# DP_TO_HDMI.net
KiCad netlist of a schematic drawn in Altium Designer
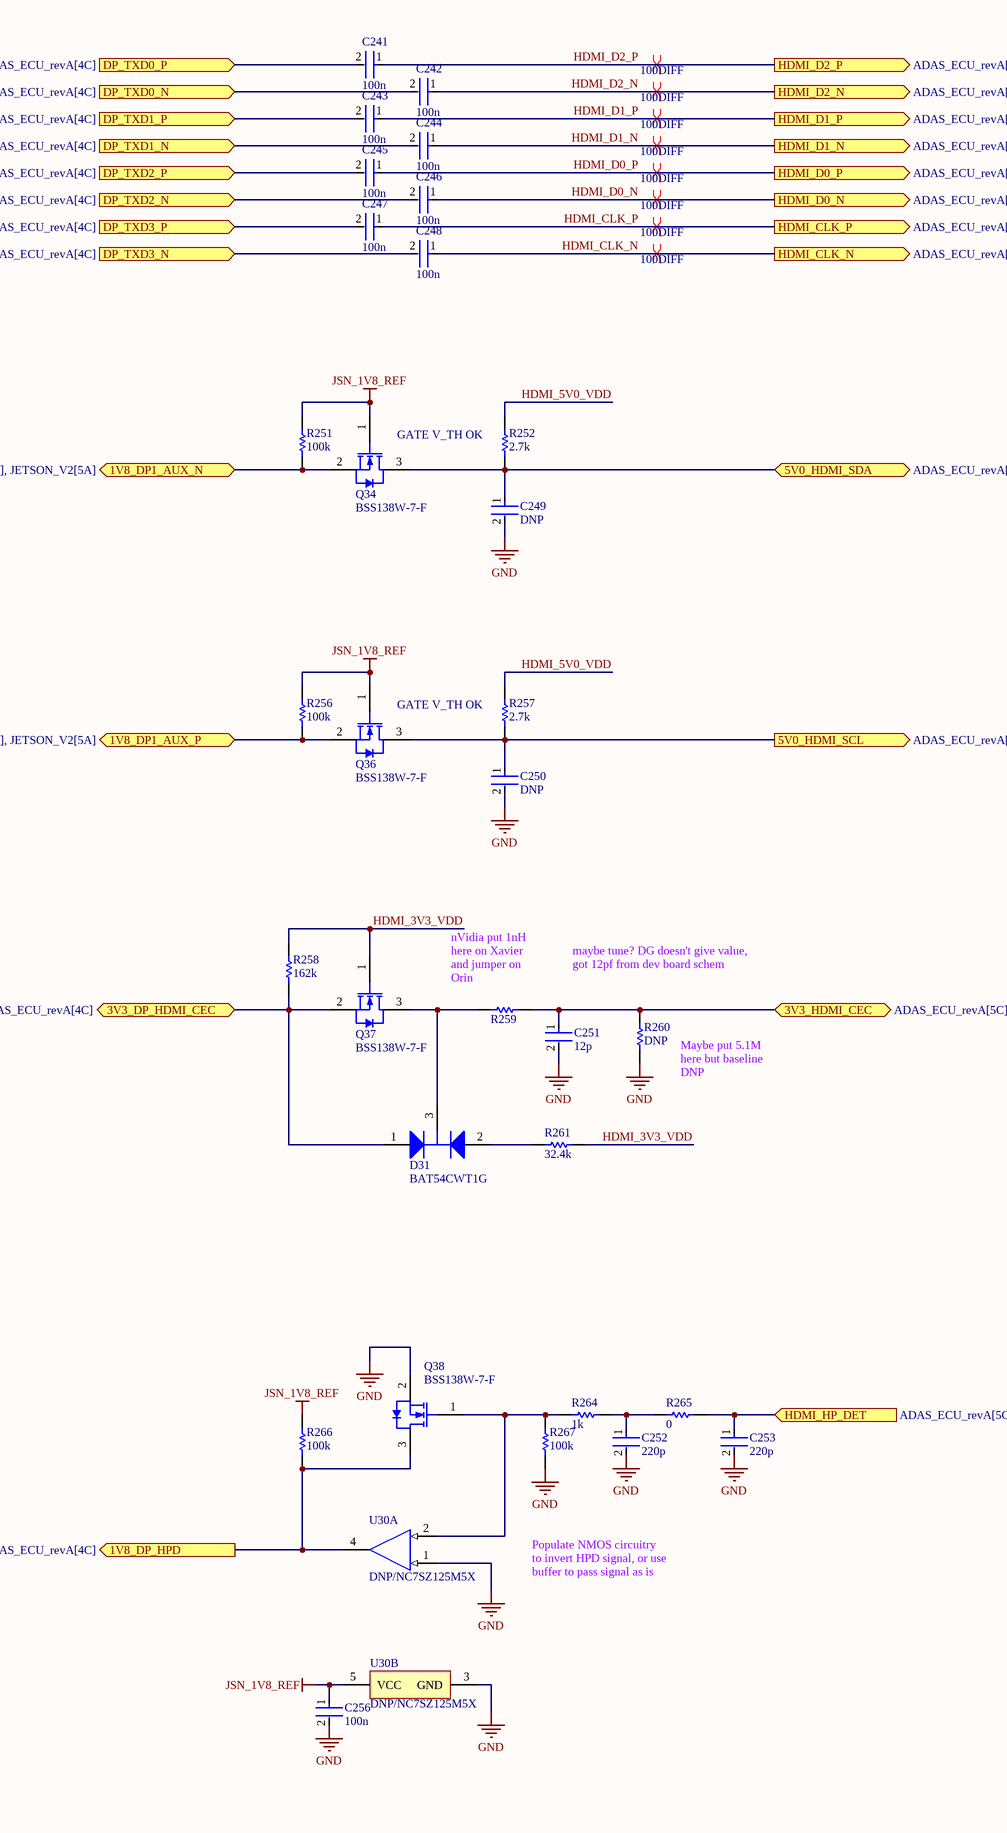
[diagram p0: DP_TO_HDMI.SchDoc, left]
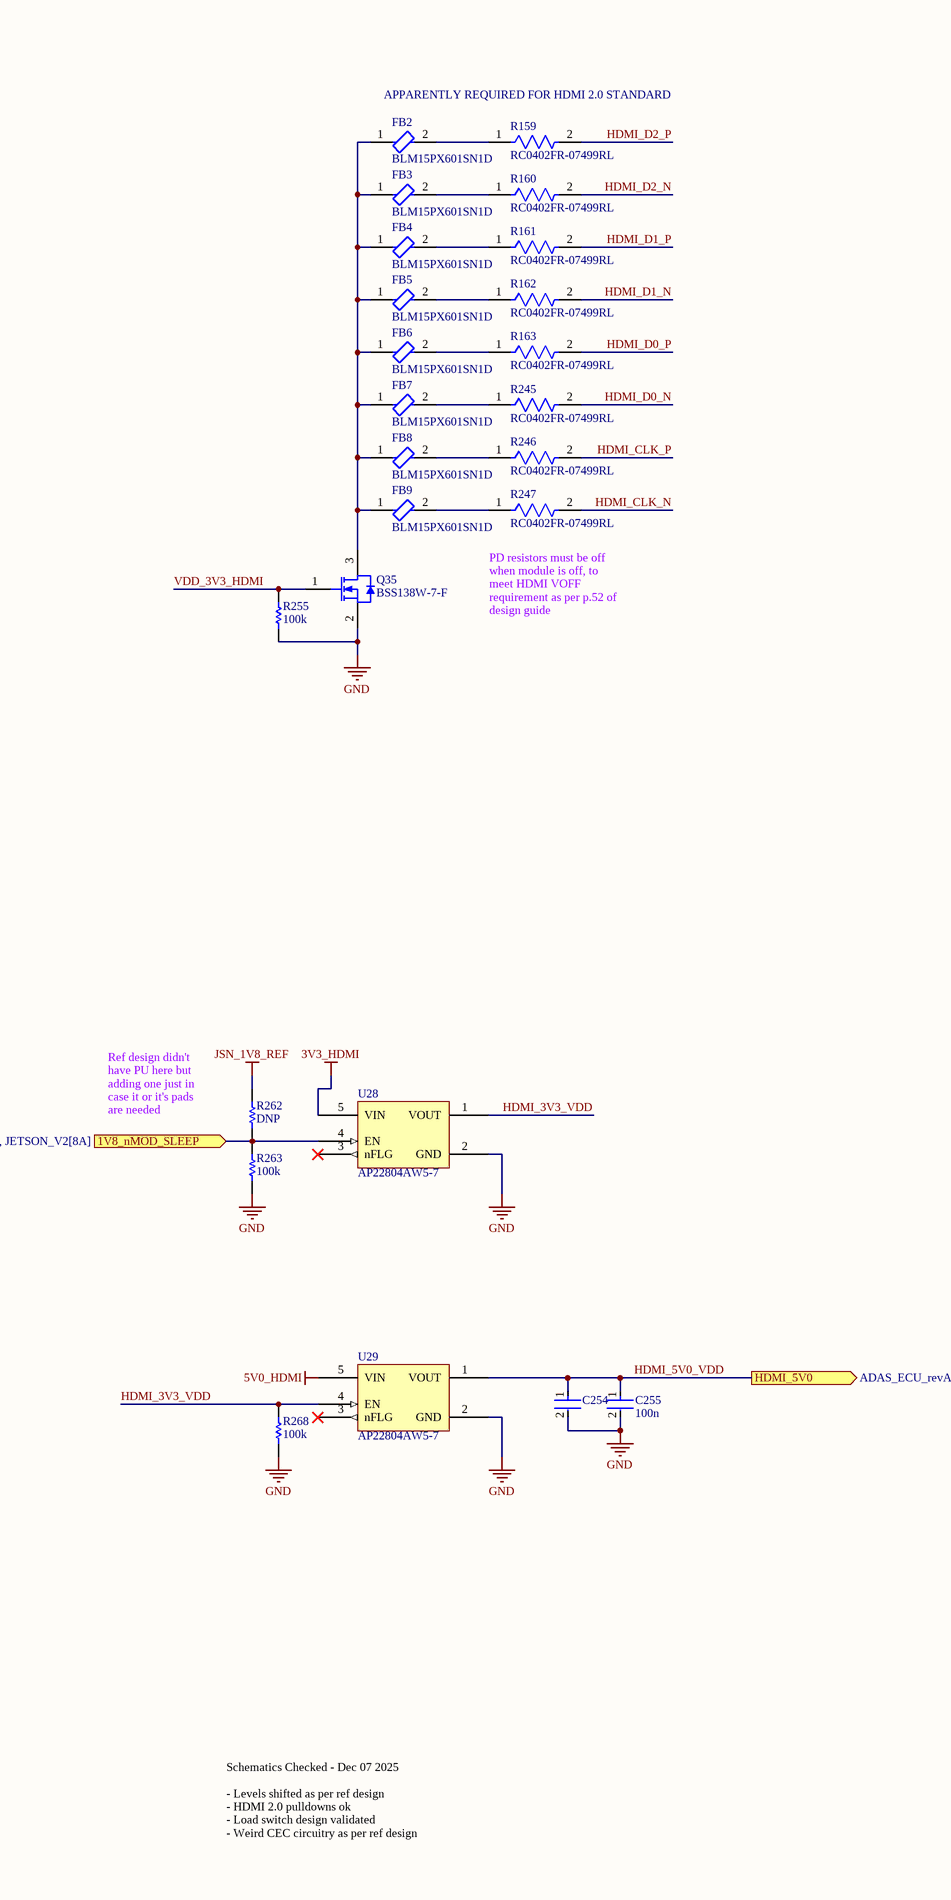
[diagram p1: DP_TO_HDMI.SchDoc, right]

(export (version "E")
  (design (tool "Eeschema 10.0.6"))
  (components
    (comp (ref "C241")
      (value "100n")
      (footprint "FP-0402-L_1_0_0_05-W_0_5-IPC_A")
      (description "LARGE PADS, 0402 CAP, CHANGE COMMENT TO MATCH REAL P/N")
      (libsource (lib "Space Concordia") (part "b4654b650e69147ec39a6b967a45e02"))
    )
    (comp (ref "C242")
      (value "100n")
      (footprint "FP-0402-L_1_0_0_05-W_0_5-IPC_A")
      (description "LARGE PADS, 0402 CAP, CHANGE COMMENT TO MATCH REAL P/N")
      (libsource (lib "Space Concordia") (part "b4654b650e69147ec39a6b967a45e02"))
    )
    (comp (ref "C243")
      (value "100n")
      (footprint "FP-0402-L_1_0_0_05-W_0_5-IPC_A")
      (description "LARGE PADS, 0402 CAP, CHANGE COMMENT TO MATCH REAL P/N")
      (libsource (lib "Space Concordia") (part "b4654b650e69147ec39a6b967a45e02"))
    )
    (comp (ref "C244")
      (value "100n")
      (footprint "FP-0402-L_1_0_0_05-W_0_5-IPC_A")
      (description "LARGE PADS, 0402 CAP, CHANGE COMMENT TO MATCH REAL P/N")
      (libsource (lib "Space Concordia") (part "b4654b650e69147ec39a6b967a45e02"))
    )
    (comp (ref "C245")
      (value "100n")
      (footprint "FP-0402-L_1_0_0_05-W_0_5-IPC_A")
      (description "LARGE PADS, 0402 CAP, CHANGE COMMENT TO MATCH REAL P/N")
      (libsource (lib "Space Concordia") (part "b4654b650e69147ec39a6b967a45e02"))
    )
    (comp (ref "C246")
      (value "100n")
      (footprint "FP-0402-L_1_0_0_05-W_0_5-IPC_A")
      (description "LARGE PADS, 0402 CAP, CHANGE COMMENT TO MATCH REAL P/N")
      (libsource (lib "Space Concordia") (part "b4654b650e69147ec39a6b967a45e02"))
    )
    (comp (ref "C247")
      (value "100n")
      (footprint "FP-0402-L_1_0_0_05-W_0_5-IPC_A")
      (description "LARGE PADS, 0402 CAP, CHANGE COMMENT TO MATCH REAL P/N")
      (libsource (lib "Space Concordia") (part "b4654b650e69147ec39a6b967a45e02"))
    )
    (comp (ref "C248")
      (value "100n")
      (footprint "FP-0402-L_1_0_0_05-W_0_5-IPC_A")
      (description "LARGE PADS, 0402 CAP, CHANGE COMMENT TO MATCH REAL P/N")
      (libsource (lib "Space Concordia") (part "b4654b650e69147ec39a6b967a45e02"))
    )
    (comp (ref "C249")
      (value "DNP")
      (footprint "FP-0402-L_1_0_0_05-W_0_5-IPC_A")
      (description "LARGE PADS, 0402 CAP, CHANGE COMMENT TO MATCH REAL P/N")
      (libsource (lib "Space Concordia") (part "b4654b650e69147ec39a6b967a45e02"))
    )
    (comp (ref "C250")
      (value "DNP")
      (footprint "FP-0402-L_1_0_0_05-W_0_5-IPC_A")
      (description "LARGE PADS, 0402 CAP, CHANGE COMMENT TO MATCH REAL P/N")
      (libsource (lib "Space Concordia") (part "b4654b650e69147ec39a6b967a45e02"))
    )
    (comp (ref "C251")
      (value "12p")
      (footprint "FP-0402-L_1_0_0_05-W_0_5-IPC_A")
      (description "LARGE PADS, 0402 CAP, CHANGE COMMENT TO MATCH REAL P/N")
      (libsource (lib "Space Concordia") (part "b4654b650e69147ec39a6b967a45e02"))
    )
    (comp (ref "C252")
      (value "220p")
      (footprint "FP-0402-L_1_0_0_05-W_0_5-IPC_A")
      (description "LARGE PADS, 0402 CAP, CHANGE COMMENT TO MATCH REAL P/N")
      (libsource (lib "Space Concordia") (part "b4654b650e69147ec39a6b967a45e02"))
    )
    (comp (ref "C253")
      (value "220p")
      (footprint "FP-0402-L_1_0_0_05-W_0_5-IPC_A")
      (description "LARGE PADS, 0402 CAP, CHANGE COMMENT TO MATCH REAL P/N")
      (libsource (lib "Space Concordia") (part "b4654b650e69147ec39a6b967a45e02"))
    )
    (comp (ref "C254")
      (value "DNP/GRM188R60J106ME47D")
      (footprint "FP-GRM188-0_1-e0_2_0_55-IPC_A")
      (description "Chip Multilayer Ceramic Capacitors for General Purpose, 0603, 10uF, X5R, 15%, 20%, 6.3V")
      (fields (field (name "VOLTAGE") "6.3V") (field (name "TOLERANCE") "20%"))
      (libsource (lib "Altium Content Vault") (part "02cd4be3c70576c341d710602a673aa"))
    )
    (comp (ref "C255")
      (value "100n")
      (footprint "FP-0402-L_1_0_0_05-W_0_5-IPC_A")
      (description "LARGE PADS, 0402 CAP, CHANGE COMMENT TO MATCH REAL P/N")
      (libsource (lib "Space Concordia") (part "b4654b650e69147ec39a6b967a45e02"))
    )
    (comp (ref "C256")
      (value "100n")
      (footprint "FP-0402-L_1_0_0_05-W_0_5-IPC_A")
      (description "LARGE PADS, 0402 CAP, CHANGE COMMENT TO MATCH REAL P/N")
      (libsource (lib "Space Concordia") (part "b4654b650e69147ec39a6b967a45e02"))
    )
    (comp (ref "D31")
      (value "BAT54CWT1G")
      (footprint "ONSC-SOT-323-3-419-04_V")
      (description "Dual Series Cathode Schottky Barrier Diodes, 3-Pin SOT-323, Pb-Free, Tape and Reel")
      (fields (field (name "MANUFACTURER") "On Semiconductor"))
      (libsource (lib "Altium Content Vault") (part "ONSC-D-A1A2K3-3"))
    )
    (comp (ref "FB2")
      (value "BLM15PX601SN1D")
      (footprint "FP-BLM15-0_05-MFG")
      (description "Chip Ferrite Bead, 0402, 600Ω @ 100MHz, 0.23Ω, 25%, 900mA")
      (fields (field (name "TOLERANCE") "25%"))
      (libsource (lib "Altium Content Vault") (part "5f30dd21d616792df468990f7003faa"))
    )
    (comp (ref "FB3")
      (value "BLM15PX601SN1D")
      (footprint "FP-BLM15-0_05-MFG")
      (description "Chip Ferrite Bead, 0402, 600Ω @ 100MHz, 0.23Ω, 25%, 900mA")
      (fields (field (name "TOLERANCE") "25%"))
      (libsource (lib "Altium Content Vault") (part "5f30dd21d616792df468990f7003faa"))
    )
    (comp (ref "FB4")
      (value "BLM15PX601SN1D")
      (footprint "FP-BLM15-0_05-MFG")
      (description "Chip Ferrite Bead, 0402, 600Ω @ 100MHz, 0.23Ω, 25%, 900mA")
      (fields (field (name "TOLERANCE") "25%"))
      (libsource (lib "Altium Content Vault") (part "5f30dd21d616792df468990f7003faa"))
    )
    (comp (ref "FB5")
      (value "BLM15PX601SN1D")
      (footprint "FP-BLM15-0_05-MFG")
      (description "Chip Ferrite Bead, 0402, 600Ω @ 100MHz, 0.23Ω, 25%, 900mA")
      (fields (field (name "TOLERANCE") "25%"))
      (libsource (lib "Altium Content Vault") (part "5f30dd21d616792df468990f7003faa"))
    )
    (comp (ref "FB6")
      (value "BLM15PX601SN1D")
      (footprint "FP-BLM15-0_05-MFG")
      (description "Chip Ferrite Bead, 0402, 600Ω @ 100MHz, 0.23Ω, 25%, 900mA")
      (fields (field (name "TOLERANCE") "25%"))
      (libsource (lib "Altium Content Vault") (part "5f30dd21d616792df468990f7003faa"))
    )
    (comp (ref "FB7")
      (value "BLM15PX601SN1D")
      (footprint "FP-BLM15-0_05-MFG")
      (description "Chip Ferrite Bead, 0402, 600Ω @ 100MHz, 0.23Ω, 25%, 900mA")
      (fields (field (name "TOLERANCE") "25%"))
      (libsource (lib "Altium Content Vault") (part "5f30dd21d616792df468990f7003faa"))
    )
    (comp (ref "FB8")
      (value "BLM15PX601SN1D")
      (footprint "FP-BLM15-0_05-MFG")
      (description "Chip Ferrite Bead, 0402, 600Ω @ 100MHz, 0.23Ω, 25%, 900mA")
      (fields (field (name "TOLERANCE") "25%"))
      (libsource (lib "Altium Content Vault") (part "5f30dd21d616792df468990f7003faa"))
    )
    (comp (ref "FB9")
      (value "BLM15PX601SN1D")
      (footprint "FP-BLM15-0_05-MFG")
      (description "Chip Ferrite Bead, 0402, 600Ω @ 100MHz, 0.23Ω, 25%, 900mA")
      (fields (field (name "TOLERANCE") "25%"))
      (libsource (lib "Altium Content Vault") (part "5f30dd21d616792df468990f7003faa"))
    )
    (comp (ref "Q34")
      (value "BSS138W-7-F")
      (footprint "DIOD-SOT323-3_V")
      (fields (field (name "MANUFACTURER") "DiodesIncorporated"))
      (libsource (lib "Altium Content Vault") (part "NEMOS-GSD-3"))
    )
    (comp (ref "Q35")
      (value "BSS138W-7-F")
      (footprint "DIOD-SOT323-3_V")
      (fields (field (name "MANUFACTURER") "DiodesIncorporated"))
      (libsource (lib "Altium Content Vault") (part "NEMOS-GSD-3"))
    )
    (comp (ref "Q36")
      (value "BSS138W-7-F")
      (footprint "DIOD-SOT323-3_V")
      (fields (field (name "MANUFACTURER") "DiodesIncorporated"))
      (libsource (lib "Altium Content Vault") (part "NEMOS-GSD-3"))
    )
    (comp (ref "Q37")
      (value "BSS138W-7-F")
      (footprint "DIOD-SOT323-3_V")
      (fields (field (name "MANUFACTURER") "DiodesIncorporated"))
      (libsource (lib "Altium Content Vault") (part "NEMOS-GSD-3"))
    )
    (comp (ref "Q38")
      (value "BSS138W-7-F")
      (footprint "DIOD-SOT323-3_V")
      (fields (field (name "MANUFACTURER") "DiodesIncorporated"))
      (libsource (lib "Altium Content Vault") (part "NEMOS-GSD-3"))
    )
    (comp (ref "R159")
      (value "RC0402FR-07499RL")
      (footprint "FP-RC0402-0_4-IPC_A")
      (description "RES 499 OHM 1% 1/16W 0402")
      (fields (field (name "TOLERANCE") "1%"))
      (libsource (lib "Altium Content Vault") (part "1029c3af85768c4190bb7ad29bc67b5"))
    )
    (comp (ref "R160")
      (value "RC0402FR-07499RL")
      (footprint "FP-RC0402-0_4-IPC_A")
      (description "RES 499 OHM 1% 1/16W 0402")
      (fields (field (name "TOLERANCE") "1%"))
      (libsource (lib "Altium Content Vault") (part "1029c3af85768c4190bb7ad29bc67b5"))
    )
    (comp (ref "R161")
      (value "RC0402FR-07499RL")
      (footprint "FP-RC0402-0_4-IPC_A")
      (description "RES 499 OHM 1% 1/16W 0402")
      (fields (field (name "TOLERANCE") "1%"))
      (libsource (lib "Altium Content Vault") (part "1029c3af85768c4190bb7ad29bc67b5"))
    )
    (comp (ref "R162")
      (value "RC0402FR-07499RL")
      (footprint "FP-RC0402-0_4-IPC_A")
      (description "RES 499 OHM 1% 1/16W 0402")
      (fields (field (name "TOLERANCE") "1%"))
      (libsource (lib "Altium Content Vault") (part "1029c3af85768c4190bb7ad29bc67b5"))
    )
    (comp (ref "R163")
      (value "RC0402FR-07499RL")
      (footprint "FP-RC0402-0_4-IPC_A")
      (description "RES 499 OHM 1% 1/16W 0402")
      (fields (field (name "TOLERANCE") "1%"))
      (libsource (lib "Altium Content Vault") (part "1029c3af85768c4190bb7ad29bc67b5"))
    )
    (comp (ref "R245")
      (value "RC0402FR-07499RL")
      (footprint "FP-RC0402-0_4-IPC_A")
      (description "RES 499 OHM 1% 1/16W 0402")
      (fields (field (name "TOLERANCE") "1%"))
      (libsource (lib "Altium Content Vault") (part "1029c3af85768c4190bb7ad29bc67b5"))
    )
    (comp (ref "R246")
      (value "RC0402FR-07499RL")
      (footprint "FP-RC0402-0_4-IPC_A")
      (description "RES 499 OHM 1% 1/16W 0402")
      (fields (field (name "TOLERANCE") "1%"))
      (libsource (lib "Altium Content Vault") (part "1029c3af85768c4190bb7ad29bc67b5"))
    )
    (comp (ref "R247")
      (value "RC0402FR-07499RL")
      (footprint "FP-RC0402-0_4-IPC_A")
      (description "RES 499 OHM 1% 1/16W 0402")
      (fields (field (name "TOLERANCE") "1%"))
      (libsource (lib "Altium Content Vault") (part "1029c3af85768c4190bb7ad29bc67b5"))
    )
    (comp (ref "R251")
      (value "100k")
      (footprint "R0603B")
      (description "Resistor")
      (libsource (lib "Space Concordia") (part "Resistor"))
    )
    (comp (ref "R252")
      (value "2.7k")
      (footprint "R0603B")
      (description "Resistor")
      (libsource (lib "Space Concordia") (part "Resistor"))
    )
    (comp (ref "R255")
      (value "100k")
      (footprint "R0603B")
      (description "Resistor")
      (libsource (lib "Space Concordia") (part "Resistor"))
    )
    (comp (ref "R256")
      (value "100k")
      (footprint "R0603B")
      (description "Resistor")
      (libsource (lib "Space Concordia") (part "Resistor"))
    )
    (comp (ref "R257")
      (value "2.7k")
      (footprint "R0603B")
      (description "Resistor")
      (libsource (lib "Space Concordia") (part "Resistor"))
    )
    (comp (ref "R258")
      (value "162k")
      (footprint "R0603B")
      (description "Resistor")
      (libsource (lib "Space Concordia") (part "Resistor"))
    )
    (comp (ref "R259")
      (value "0402 JUMPER")
      (footprint "RESC1005X40X25ML05T05")
      (description "READ THE NAME")
      (libsource (lib "Space Concordia") (part "CMP-009-00206-2"))
    )
    (comp (ref "R260")
      (value "DNP")
      (footprint "R0603B")
      (description "Resistor")
      (libsource (lib "Space Concordia") (part "Resistor"))
    )
    (comp (ref "R261")
      (value "32.4k")
      (footprint "R0603B")
      (description "Resistor")
      (libsource (lib "Space Concordia") (part "Resistor"))
    )
    (comp (ref "R262")
      (value "DNP")
      (footprint "R0603B")
      (description "Resistor")
      (libsource (lib "Space Concordia") (part "Resistor"))
    )
    (comp (ref "R263")
      (value "100k")
      (footprint "R0603B")
      (description "Resistor")
      (libsource (lib "Space Concordia") (part "Resistor"))
    )
    (comp (ref "R264")
      (value "1k")
      (footprint "R0603B")
      (description "Resistor")
      (libsource (lib "Space Concordia") (part "Resistor"))
    )
    (comp (ref "R265")
      (value "0")
      (footprint "R0603B")
      (description "Resistor")
      (libsource (lib "Space Concordia") (part "Resistor"))
    )
    (comp (ref "R266")
      (value "100k")
      (footprint "R0603B")
      (description "Resistor")
      (libsource (lib "Space Concordia") (part "Resistor"))
    )
    (comp (ref "R267")
      (value "100k")
      (footprint "R0603B")
      (description "Resistor")
      (libsource (lib "Space Concordia") (part "Resistor"))
    )
    (comp (ref "R268")
      (value "100k")
      (footprint "R0603B")
      (description "Resistor")
      (libsource (lib "Space Concordia") (part "Resistor"))
    )
    (comp (ref "U28")
      (value "AP22804AW5-7")
      (footprint "SOT95P285X140-5N")
      (description "SINGLE CHANNEL POWER DISTRIBUTION LOAD SWITCH, -40 to 85°C pF, RoHS")
      (libsource (lib "Space Concordia") (part "AP22804AW5-7"))
    )
    (comp (ref "U29")
      (value "AP22804AW5-7")
      (footprint "SOT95P285X140-5N")
      (description "SINGLE CHANNEL POWER DISTRIBUTION LOAD SWITCH, -40 to 85°C pF, RoHS")
      (libsource (lib "Space Concordia") (part "AP22804AW5-7"))
    )
    (comp (ref "U30")
      (value "DNP/NC7SZ125M5X")
      (footprint "FAIR-SOT23-5_V")
      (fields (field (name "MANUFACTURER") "Fairchild Semiconductor"))
      (libsource (lib "") (part "FAIR-NC7SZ125-SOT23-5_1"))
    )
  )
  (nets
    (net (code "1") (name "/1V8_DP1_AUX_N") (class "Default")
      (node (ref "Q34") (pin "2") (pinfunction "S_2") (pintype "passive"))
      (node (ref "R251") (pin "1") (pinfunction "1_1") (pintype "passive"))
    )
    (net (code "2") (name "/1V8_DP1_AUX_P") (class "Default")
      (node (ref "Q36") (pin "2") (pinfunction "S_2") (pintype "passive"))
      (node (ref "R256") (pin "1") (pinfunction "1_1") (pintype "passive"))
    )
    (net (code "3") (name "/1V8_DP_HPD") (class "Default")
      (node (ref "Q38") (pin "3") (pinfunction "D_3") (pintype "passive"))
      (node (ref "R266") (pin "1") (pinfunction "1_1") (pintype "passive"))
      (node (ref "U30") (pin "4") (pinfunction "Y_4") (pintype "tri_state"))
    )
    (net (code "4") (name "/1V8_nMOD_SLEEP") (class "Default")
      (node (ref "R262") (pin "1") (pinfunction "1_1") (pintype "passive"))
      (node (ref "R263") (pin "2") (pinfunction "2_2") (pintype "passive"))
      (node (ref "U28") (pin "4") (pinfunction "EN_4") (pintype "input"))
    )
    (net (code "5") (name "/3V3_DP_HDMI_CEC") (class "Default")
      (node (ref "D31") (pin "1") (pinfunction "A1_1") (pintype "passive"))
      (node (ref "Q37") (pin "2") (pinfunction "S_2") (pintype "passive"))
      (node (ref "R258") (pin "2") (pinfunction "2_2") (pintype "passive"))
    )
    (net (code "6") (name "/3V3_HDMI_CEC") (class "Default")
      (node (ref "C251") (pin "1") (pinfunction "1_1") (pintype "passive"))
      (node (ref "R259") (pin "2") (pinfunction "2_2") (pintype "passive"))
      (node (ref "R260") (pin "2") (pinfunction "2_2") (pintype "passive"))
    )
    (net (code "7") (name "/5V0_HDMI_SCL") (class "Default")
      (node (ref "C250") (pin "1") (pinfunction "1_1") (pintype "passive"))
      (node (ref "Q36") (pin "3") (pinfunction "D_3") (pintype "passive"))
      (node (ref "R257") (pin "1") (pinfunction "1_1") (pintype "passive"))
    )
    (net (code "8") (name "/5V0_HDMI_SDA") (class "Default")
      (node (ref "C249") (pin "1") (pinfunction "1_1") (pintype "passive"))
      (node (ref "Q34") (pin "3") (pinfunction "D_3") (pintype "passive"))
      (node (ref "R252") (pin "1") (pinfunction "1_1") (pintype "passive"))
    )
    (net (code "9") (name "/DP_TXD0_N") (class "Default")
      (node (ref "C242") (pin "2") (pinfunction "2_2") (pintype "passive"))
    )
    (net (code "10") (name "/DP_TXD0_P") (class "Default")
      (node (ref "C241") (pin "2") (pinfunction "2_2") (pintype "passive"))
    )
    (net (code "11") (name "/DP_TXD1_N") (class "Default")
      (node (ref "C244") (pin "2") (pinfunction "2_2") (pintype "passive"))
    )
    (net (code "12") (name "/DP_TXD1_P") (class "Default")
      (node (ref "C243") (pin "2") (pinfunction "2_2") (pintype "passive"))
    )
    (net (code "13") (name "/DP_TXD2_N") (class "Default")
      (node (ref "C246") (pin "2") (pinfunction "2_2") (pintype "passive"))
    )
    (net (code "14") (name "/DP_TXD2_P") (class "Default")
      (node (ref "C245") (pin "2") (pinfunction "2_2") (pintype "passive"))
    )
    (net (code "15") (name "/DP_TXD3_N") (class "Default")
      (node (ref "C248") (pin "2") (pinfunction "2_2") (pintype "passive"))
    )
    (net (code "16") (name "/DP_TXD3_P") (class "Default")
      (node (ref "C247") (pin "2") (pinfunction "2_2") (pintype "passive"))
    )
    (net (code "17") (name "/HDMI_3V3_VDD") (class "Default")
      (node (ref "Q37") (pin "1") (pinfunction "G_1") (pintype "passive"))
      (node (ref "R258") (pin "1") (pinfunction "1_1") (pintype "passive"))
      (node (ref "R261") (pin "1") (pinfunction "1_1") (pintype "passive"))
      (node (ref "R268") (pin "2") (pinfunction "2_2") (pintype "passive"))
      (node (ref "U28") (pin "1") (pinfunction "VOUT_1") (pintype "power_in"))
      (node (ref "U29") (pin "4") (pinfunction "EN_4") (pintype "input"))
    )
    (net (code "18") (name "/HDMI_5V0_VDD") (class "Default")
      (node (ref "C254") (pin "1") (pinfunction "1_1") (pintype "passive"))
      (node (ref "C255") (pin "1") (pinfunction "1_1") (pintype "passive"))
      (node (ref "R252") (pin "2") (pinfunction "2_2") (pintype "passive"))
      (node (ref "R257") (pin "2") (pinfunction "2_2") (pintype "passive"))
      (node (ref "U29") (pin "1") (pinfunction "VOUT_1") (pintype "power_in"))
    )
    (net (code "19") (name "/HDMI_CLK_N") (class "Default")
      (node (ref "C248") (pin "1") (pinfunction "1_1") (pintype "passive"))
      (node (ref "R247") (pin "2") (pinfunction "2_2") (pintype "passive"))
    )
    (net (code "20") (name "/HDMI_CLK_P") (class "Default")
      (node (ref "C247") (pin "1") (pinfunction "1_1") (pintype "passive"))
      (node (ref "R246") (pin "2") (pinfunction "2_2") (pintype "passive"))
    )
    (net (code "21") (name "/HDMI_D0_N") (class "Default")
      (node (ref "C246") (pin "1") (pinfunction "1_1") (pintype "passive"))
      (node (ref "R245") (pin "2") (pinfunction "2_2") (pintype "passive"))
    )
    (net (code "22") (name "/HDMI_D0_P") (class "Default")
      (node (ref "C245") (pin "1") (pinfunction "1_1") (pintype "passive"))
      (node (ref "R163") (pin "2") (pinfunction "2_2") (pintype "passive"))
    )
    (net (code "23") (name "/HDMI_D1_N") (class "Default")
      (node (ref "C244") (pin "1") (pinfunction "1_1") (pintype "passive"))
      (node (ref "R162") (pin "2") (pinfunction "2_2") (pintype "passive"))
    )
    (net (code "24") (name "/HDMI_D1_P") (class "Default")
      (node (ref "C243") (pin "1") (pinfunction "1_1") (pintype "passive"))
      (node (ref "R161") (pin "2") (pinfunction "2_2") (pintype "passive"))
    )
    (net (code "25") (name "/HDMI_D2_N") (class "Default")
      (node (ref "C242") (pin "1") (pinfunction "1_1") (pintype "passive"))
      (node (ref "R160") (pin "2") (pinfunction "2_2") (pintype "passive"))
    )
    (net (code "26") (name "/HDMI_D2_P") (class "Default")
      (node (ref "C241") (pin "1") (pinfunction "1_1") (pintype "passive"))
      (node (ref "R159") (pin "2") (pinfunction "2_2") (pintype "passive"))
    )
    (net (code "27") (name "/HDMI_HP_DET") (class "Default")
      (node (ref "C253") (pin "1") (pinfunction "1_1") (pintype "passive"))
      (node (ref "R265") (pin "1") (pinfunction "1_1") (pintype "passive"))
    )
    (net (code "28") (name "/VDD_3V3_HDMI") (class "Default")
      (node (ref "Q35") (pin "1") (pinfunction "G_1") (pintype "passive"))
      (node (ref "R255") (pin "2") (pinfunction "2_2") (pintype "passive"))
    )
    (net (code "29") (name "3V3_HDMI") (class "Default")
      (node (ref "U28") (pin "5") (pinfunction "VIN_5") (pintype "power_in"))
    )
    (net (code "30") (name "5V0_HDMI") (class "Default")
      (node (ref "U29") (pin "5") (pinfunction "VIN_5") (pintype "power_in"))
    )
    (net (code "31") (name "GND") (class "Default")
      (node (ref "C249") (pin "2") (pinfunction "2_2") (pintype "passive"))
      (node (ref "C250") (pin "2") (pinfunction "2_2") (pintype "passive"))
      (node (ref "C251") (pin "2") (pinfunction "2_2") (pintype "passive"))
      (node (ref "C252") (pin "2") (pinfunction "2_2") (pintype "passive"))
      (node (ref "C253") (pin "2") (pinfunction "2_2") (pintype "passive"))
      (node (ref "C254") (pin "2") (pinfunction "2_2") (pintype "passive"))
      (node (ref "C255") (pin "2") (pinfunction "2_2") (pintype "passive"))
      (node (ref "C256") (pin "2") (pinfunction "2_2") (pintype "passive"))
      (node (ref "Q35") (pin "2") (pinfunction "S_2") (pintype "passive"))
      (node (ref "Q38") (pin "2") (pinfunction "S_2") (pintype "passive"))
      (node (ref "R255") (pin "1") (pinfunction "1_1") (pintype "passive"))
      (node (ref "R260") (pin "1") (pinfunction "1_1") (pintype "passive"))
      (node (ref "R263") (pin "1") (pinfunction "1_1") (pintype "passive"))
      (node (ref "R267") (pin "1") (pinfunction "1_1") (pintype "passive"))
      (node (ref "R268") (pin "1") (pinfunction "1_1") (pintype "passive"))
      (node (ref "U28") (pin "2") (pinfunction "GND_2") (pintype "power_in"))
      (node (ref "U29") (pin "2") (pinfunction "GND_2") (pintype "power_in"))
      (node (ref "U30") (pin "1") (pinfunction "~{OE}_1") (pintype "input"))
      (node (ref "U30") (pin "3") (pinfunction "GND_3") (pintype "power_in"))
    )
    (net (code "32") (name "JSN_1V8_REF") (class "Default")
      (node (ref "C256") (pin "1") (pinfunction "1_1") (pintype "passive"))
      (node (ref "Q34") (pin "1") (pinfunction "G_1") (pintype "passive"))
      (node (ref "Q36") (pin "1") (pinfunction "G_1") (pintype "passive"))
      (node (ref "R251") (pin "2") (pinfunction "2_2") (pintype "passive"))
      (node (ref "R256") (pin "2") (pinfunction "2_2") (pintype "passive"))
      (node (ref "R262") (pin "2") (pinfunction "2_2") (pintype "passive"))
      (node (ref "R266") (pin "2") (pinfunction "2_2") (pintype "passive"))
      (node (ref "U30") (pin "5") (pinfunction "VCC_5") (pintype "power_in"))
    )
    (net (code "33") (name "Net-(C252-Pad1)") (class "Default")
      (node (ref "C252") (pin "1") (pinfunction "1_1") (pintype "passive"))
      (node (ref "R264") (pin "1") (pinfunction "1_1") (pintype "passive"))
      (node (ref "R265") (pin "2") (pinfunction "2_2") (pintype "passive"))
    )
    (net (code "34") (name "Net-(D31-A2)") (class "Default")
      (node (ref "D31") (pin "2") (pinfunction "A2_2") (pintype "passive"))
      (node (ref "R261") (pin "2") (pinfunction "2_2") (pintype "passive"))
    )
    (net (code "35") (name "Net-(D31-K)") (class "Default")
      (node (ref "D31") (pin "3") (pinfunction "K_3") (pintype "passive"))
      (node (ref "Q37") (pin "3") (pinfunction "D_3") (pintype "passive"))
      (node (ref "R259") (pin "1") (pinfunction "1_1") (pintype "passive"))
    )
    (net (code "36") (name "Net-(FB2-Pad2)") (class "Default")
      (node (ref "FB2") (pin "2") (pinfunction "2_2") (pintype "passive"))
      (node (ref "R159") (pin "1") (pinfunction "1_1") (pintype "passive"))
    )
    (net (code "37") (name "Net-(FB3-Pad2)") (class "Default")
      (node (ref "FB3") (pin "2") (pinfunction "2_2") (pintype "passive"))
      (node (ref "R160") (pin "1") (pinfunction "1_1") (pintype "passive"))
    )
    (net (code "38") (name "Net-(FB4-Pad2)") (class "Default")
      (node (ref "FB4") (pin "2") (pinfunction "2_2") (pintype "passive"))
      (node (ref "R161") (pin "1") (pinfunction "1_1") (pintype "passive"))
    )
    (net (code "39") (name "Net-(FB5-Pad2)") (class "Default")
      (node (ref "FB5") (pin "2") (pinfunction "2_2") (pintype "passive"))
      (node (ref "R162") (pin "1") (pinfunction "1_1") (pintype "passive"))
    )
    (net (code "40") (name "Net-(FB6-Pad2)") (class "Default")
      (node (ref "FB6") (pin "2") (pinfunction "2_2") (pintype "passive"))
      (node (ref "R163") (pin "1") (pinfunction "1_1") (pintype "passive"))
    )
    (net (code "41") (name "Net-(FB7-Pad2)") (class "Default")
      (node (ref "FB7") (pin "2") (pinfunction "2_2") (pintype "passive"))
      (node (ref "R245") (pin "1") (pinfunction "1_1") (pintype "passive"))
    )
    (net (code "42") (name "Net-(FB8-Pad2)") (class "Default")
      (node (ref "FB8") (pin "2") (pinfunction "2_2") (pintype "passive"))
      (node (ref "R246") (pin "1") (pinfunction "1_1") (pintype "passive"))
    )
    (net (code "43") (name "Net-(FB9-Pad2)") (class "Default")
      (node (ref "FB9") (pin "2") (pinfunction "2_2") (pintype "passive"))
      (node (ref "R247") (pin "1") (pinfunction "1_1") (pintype "passive"))
    )
    (net (code "44") (name "Net-(Q35-D)") (class "Default")
      (node (ref "FB2") (pin "1") (pinfunction "1_1") (pintype "passive"))
      (node (ref "FB3") (pin "1") (pinfunction "1_1") (pintype "passive"))
      (node (ref "FB4") (pin "1") (pinfunction "1_1") (pintype "passive"))
      (node (ref "FB5") (pin "1") (pinfunction "1_1") (pintype "passive"))
      (node (ref "FB6") (pin "1") (pinfunction "1_1") (pintype "passive"))
      (node (ref "FB7") (pin "1") (pinfunction "1_1") (pintype "passive"))
      (node (ref "FB8") (pin "1") (pinfunction "1_1") (pintype "passive"))
      (node (ref "FB9") (pin "1") (pinfunction "1_1") (pintype "passive"))
      (node (ref "Q35") (pin "3") (pinfunction "D_3") (pintype "passive"))
    )
    (net (code "45") (name "Net-(Q38-G)") (class "Default")
      (node (ref "Q38") (pin "1") (pinfunction "G_1") (pintype "passive"))
      (node (ref "R264") (pin "2") (pinfunction "2_2") (pintype "passive"))
      (node (ref "R267") (pin "2") (pinfunction "2_2") (pintype "passive"))
      (node (ref "U30") (pin "2") (pinfunction "A_2") (pintype "input"))
    )
    (net (code "46") (name "unconnected-(U28-nFLG-Pad3)") (class "Default")
      (node (ref "U28") (pin "3") (pinfunction "nFLG_3") (pintype "output+no_connect"))
    )
    (net (code "47") (name "unconnected-(U29-nFLG-Pad3)") (class "Default")
      (node (ref "U29") (pin "3") (pinfunction "nFLG_3") (pintype "output+no_connect"))
    )
  )
)
